# gripper_board.net
KiCad netlist of a schematic drawn in EAGLE
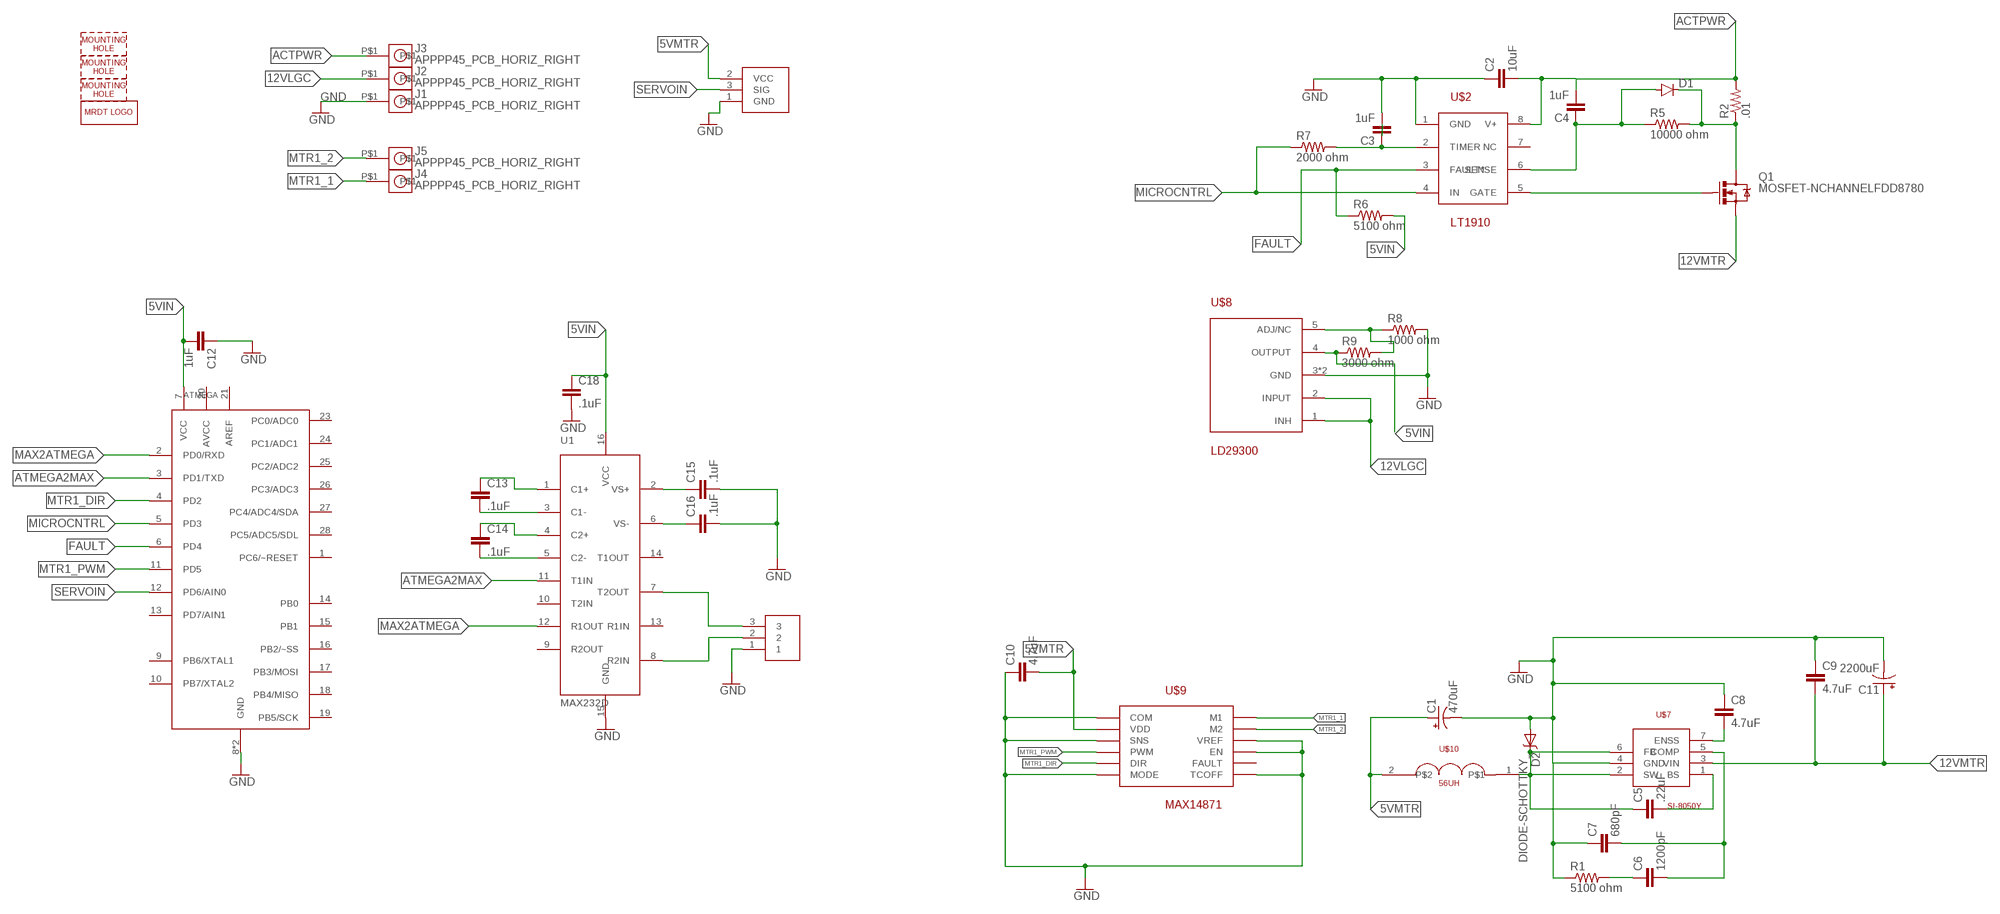
[diagram p0: schematic, sheet 1]

(export (version "E")
  (design (tool "Eeschema 10.0.6"))
  (components
    (comp (ref "ATMEGA")
      (value "Q_ATMEGA328P")
      (footprint "eagle-import:DIP28")
      (libsource (lib "eagle-import") (part "Q_ATMEGA328P"))
    )
    (comp (ref "C1")
      (value "470uF")
      (footprint "eagle-import:PANASONIC_H13")
      (libsource (lib "eagle-import") (part "100UF-ELECT"))
    )
    (comp (ref "C2")
      (value "10uF")
      (footprint "eagle-import:0603-CAP")
      (libsource (lib "eagle-import") (part "CAP0603-CAP"))
    )
    (comp (ref "C3")
      (value "1uF")
      (footprint "eagle-import:0603-CAP")
      (libsource (lib "eagle-import") (part "CAP0603-CAP"))
    )
    (comp (ref "C4")
      (value "1uF")
      (footprint "eagle-import:0603-CAP")
      (libsource (lib "eagle-import") (part "CAP0603-CAP"))
    )
    (comp (ref "C5")
      (value ".22uF")
      (footprint "eagle-import:1206")
      (libsource (lib "eagle-import") (part "1.0UF50V10%(1206)"))
    )
    (comp (ref "C6")
      (value "1200pF")
      (footprint "eagle-import:1206")
      (libsource (lib "eagle-import") (part "1.0UF50V10%(1206)"))
    )
    (comp (ref "C7")
      (value "680pF")
      (footprint "eagle-import:1206")
      (libsource (lib "eagle-import") (part "1.0UF50V10%(1206)"))
    )
    (comp (ref "C8")
      (value "4.7uF")
      (footprint "eagle-import:1206")
      (libsource (lib "eagle-import") (part "1.0UF50V10%(1206)"))
    )
    (comp (ref "C9")
      (value "4.7uF")
      (footprint "eagle-import:1206")
      (libsource (lib "eagle-import") (part "1.0UF50V10%(1206)"))
    )
    (comp (ref "C10")
      (value "4.7uF")
      (footprint "eagle-import:1206")
      (libsource (lib "eagle-import") (part "1.0UF50V10%(1206)"))
    )
    (comp (ref "C11")
      (value "2200uF")
      (footprint "eagle-import:C_16MM")
      (libsource (lib "eagle-import") (part "C_108CKH050M"))
    )
    (comp (ref "C12")
      (value "1uF")
      (footprint "eagle-import:0603-CAP")
      (libsource (lib "eagle-import") (part "CAP0603-CAP"))
    )
    (comp (ref "C13")
      (value ".1uF")
      (footprint "eagle-import:0805")
      (libsource (lib "eagle-import") (part "22UF-6.3V-20%(0805)"))
    )
    (comp (ref "C14")
      (value ".1uF")
      (footprint "eagle-import:0805")
      (libsource (lib "eagle-import") (part "22UF-6.3V-20%(0805)"))
    )
    (comp (ref "C15")
      (value ".1uF")
      (footprint "eagle-import:0805")
      (libsource (lib "eagle-import") (part "22UF-6.3V-20%(0805)"))
    )
    (comp (ref "C16")
      (value ".1uF")
      (footprint "eagle-import:0805")
      (libsource (lib "eagle-import") (part "22UF-6.3V-20%(0805)"))
    )
    (comp (ref "C18")
      (value ".1uF")
      (footprint "eagle-import:0805")
      (libsource (lib "eagle-import") (part "22UF-6.3V-20%(0805)"))
    )
    (comp (ref "D1")
      (value "DIODESMA")
      (footprint "eagle-import:SMA-DIODE")
      (libsource (lib "eagle-import") (part "DIODESMA"))
    )
    (comp (ref "D2")
      (value "DIODE-SCHOTTKY_")
      (footprint "eagle-import:SMA-DIODE")
      (libsource (lib "eagle-import") (part "DIODE-SCHOTTKY_"))
    )
    (comp (ref "H1")
      (value "MOUNTING_HOLE#4")
      (footprint "eagle-import:#4_SCREW")
      (libsource (lib "eagle-import") (part "MOUNTING_HOLE#4"))
    )
    (comp (ref "H2")
      (value "MOUNTING_HOLE#4")
      (footprint "eagle-import:#4_SCREW")
      (libsource (lib "eagle-import") (part "MOUNTING_HOLE#4"))
    )
    (comp (ref "H3")
      (value "MOUNTING_HOLE#4")
      (footprint "eagle-import:#4_SCREW")
      (libsource (lib "eagle-import") (part "MOUNTING_HOLE#4"))
    )
    (comp (ref "J1")
      (value "APPPP45_PCB_HORIZ_RIGHT")
      (footprint "eagle-import:APP45_PCB_HORIZ_RIGHT")
      (libsource (lib "eagle-import") (part "APPPP45_PCB_HORIZ_RIGHT"))
    )
    (comp (ref "J2")
      (value "APPPP45_PCB_HORIZ_RIGHT")
      (footprint "eagle-import:APP45_PCB_HORIZ_RIGHT")
      (libsource (lib "eagle-import") (part "APPPP45_PCB_HORIZ_RIGHT"))
    )
    (comp (ref "J3")
      (value "APPPP45_PCB_HORIZ_RIGHT")
      (footprint "eagle-import:APP45_PCB_HORIZ_RIGHT")
      (libsource (lib "eagle-import") (part "APPPP45_PCB_HORIZ_RIGHT"))
    )
    (comp (ref "J4")
      (value "APPPP45_PCB_HORIZ_RIGHT")
      (footprint "eagle-import:APP45_PCB_HORIZ_RIGHT")
      (libsource (lib "eagle-import") (part "APPPP45_PCB_HORIZ_RIGHT"))
    )
    (comp (ref "J5")
      (value "APPPP45_PCB_HORIZ_RIGHT")
      (footprint "eagle-import:APP45_PCB_HORIZ_RIGHT")
      (libsource (lib "eagle-import") (part "APPPP45_PCB_HORIZ_RIGHT"))
    )
    (comp (ref "J6")
      (value "SL03")
      (footprint "eagle-import:MOLEX-70543-0002")
      (libsource (lib "eagle-import") (part "SL03"))
    )
    (comp (ref "LOGO1")
      (value "MRDT_LOGO")
      (footprint "eagle-import:MRDT_LOGO")
      (libsource (lib "eagle-import") (part "MRDT_LOGO"))
    )
    (comp (ref "Q1")
      (value "MOSFET-NCHANNELFDD8780")
      (footprint "eagle-import:DPAK")
      (libsource (lib "eagle-import") (part "MOSFET-NCHANNELFDD8780"))
    )
    (comp (ref "R1")
      (value "5100 ohm")
      (footprint "eagle-import:0603-RES")
      (libsource (lib "eagle-import") (part "RESISTOR0603-RES"))
    )
    (comp (ref "R2")
      (value ".01")
      (footprint "eagle-import:1206")
      (libsource (lib "eagle-import") (part "SparkFun-Resistors_RESISTOR1206"))
    )
    (comp (ref "R5")
      (value "10000 ohm")
      (footprint "eagle-import:0603-RES")
      (libsource (lib "eagle-import") (part "RESISTOR0603-RES"))
    )
    (comp (ref "R6")
      (value "5100 ohm")
      (footprint "eagle-import:0603-RES")
      (libsource (lib "eagle-import") (part "RESISTOR0603-RES"))
    )
    (comp (ref "R7")
      (value "2000 ohm")
      (footprint "eagle-import:0603-RES")
      (libsource (lib "eagle-import") (part "RESISTOR0603-RES"))
    )
    (comp (ref "R8")
      (value "1000 ohm")
      (footprint "eagle-import:0603-RES")
      (libsource (lib "eagle-import") (part "RESISTOR0603-RES"))
    )
    (comp (ref "R9")
      (value "3000 ohm")
      (footprint "eagle-import:0603-RES")
      (libsource (lib "eagle-import") (part "RESISTOR0603-RES"))
    )
    (comp (ref "U$1")
      (value "SERVOMOLEX_SL_VERT_TH")
      (footprint "eagle-import:MOLEX-70543-0002")
      (libsource (lib "eagle-import") (part "SERVOMOLEX_SL_VERT_TH"))
    )
    (comp (ref "U$2")
      (value "LT1910")
      (footprint "eagle-import:SOIC8")
      (libsource (lib "eagle-import") (part "LT1910"))
    )
    (comp (ref "U$7")
      (value "SI-8050Y")
      (footprint "eagle-import:TO-220-7")
      (libsource (lib "eagle-import") (part "SI-8050Y"))
    )
    (comp (ref "U$8")
      (value "LD29300")
      (footprint "eagle-import:P2PAK")
      (libsource (lib "eagle-import") (part "LD29300"))
    )
    (comp (ref "U$9")
      (value "MAX14871")
      (footprint "eagle-import:TSSOP-16")
      (libsource (lib "eagle-import") (part "MAX14871"))
    )
    (comp (ref "U$10")
      (value "56UH")
      (footprint "eagle-import:1210")
      (libsource (lib "eagle-import") (part "56UH"))
    )
    (comp (ref "U1")
      (value "MAX232D")
      (footprint "eagle-import:SOIC16")
      (libsource (lib "eagle-import") (part "MAX232D"))
    )
  )
  (nets
    (net (code "1") (name "5VIN") (class "Default")
      (node (ref "ATMEGA") (pin "7") (pinfunction "VCC_7") (pintype "bidirectional"))
      (node (ref "C12") (pin "2") (pinfunction "2_2") (pintype "passive"))
      (node (ref "C18") (pin "1") (pinfunction "1_1") (pintype "passive"))
      (node (ref "R6") (pin "2") (pinfunction "2_2") (pintype "passive"))
      (node (ref "R9") (pin "1") (pinfunction "1_1") (pintype "passive"))
      (node (ref "U$8") (pin "4") (pinfunction "OUTPUT_4") (pintype "bidirectional"))
      (node (ref "U1") (pin "16") (pinfunction "VCC_16") (pintype "bidirectional"))
    )
    (net (code "2") (name "5VMTR") (class "Default")
      (node (ref "C1") (pin "+") (pinfunction "+_+") (pintype "passive"))
      (node (ref "C10") (pin "2") (pinfunction "2_2") (pintype "passive"))
      (node (ref "U$1") (pin "2") (pinfunction "VCC_2") (pintype "bidirectional"))
      (node (ref "U$10") (pin "2") (pinfunction "P$2_2") (pintype "bidirectional"))
      (node (ref "U$9") (pin "13") (pinfunction "VDD_13") (pintype "bidirectional"))
      (node (ref "U$9") (pin "4") (pinfunction "VDD_4") (pintype "bidirectional"))
    )
    (net (code "3") (name "12VLGC") (class "Default")
      (node (ref "J2") (pin "P$1") (pinfunction "P$1_P$1") (pintype "bidirectional"))
      (node (ref "U$8") (pin "1") (pinfunction "INH_1") (pintype "bidirectional"))
      (node (ref "U$8") (pin "2") (pinfunction "INPUT_2") (pintype "bidirectional"))
    )
    (net (code "4") (name "12VMTR") (class "Default")
      (node (ref "C11") (pin "+") (pinfunction "+_+") (pintype "passive"))
      (node (ref "C9") (pin "2") (pinfunction "2_2") (pintype "passive"))
      (node (ref "Q1") (pin "3") (pinfunction "S_3") (pintype "passive"))
      (node (ref "U$7") (pin "3") (pinfunction "VIN_3") (pintype "bidirectional"))
    )
    (net (code "5") (name "ACTPWR") (class "Default")
      (node (ref "C2") (pin "2") (pinfunction "2_2") (pintype "passive"))
      (node (ref "C4") (pin "2") (pinfunction "2_2") (pintype "passive"))
      (node (ref "J3") (pin "P$1") (pinfunction "P$1_P$1") (pintype "bidirectional"))
      (node (ref "R2") (pin "2") (pinfunction "2_2") (pintype "passive"))
      (node (ref "U$2") (pin "8") (pinfunction "V+_8") (pintype "bidirectional"))
    )
    (net (code "6") (name "ATMEGA2MAX") (class "Default")
      (node (ref "ATMEGA") (pin "3") (pinfunction "PD1/TXD_3") (pintype "bidirectional"))
      (node (ref "U1") (pin "11") (pinfunction "T1IN_11") (pintype "bidirectional"))
    )
    (net (code "7") (name "FAULT") (class "Default")
      (node (ref "ATMEGA") (pin "6") (pinfunction "PD4_6") (pintype "bidirectional"))
      (node (ref "R6") (pin "1") (pinfunction "1_1") (pintype "passive"))
      (node (ref "U$2") (pin "3") (pinfunction "FAULT*_3") (pintype "bidirectional"))
    )
    (net (code "8") (name "GND") (class "Default")
      (node (ref "ATMEGA") (pin "22") (pinfunction "GND_22") (pintype "bidirectional"))
      (node (ref "ATMEGA") (pin "8") (pinfunction "GND_8") (pintype "bidirectional"))
      (node (ref "C1") (pin "-") (pinfunction "-_-") (pintype "passive"))
      (node (ref "C10") (pin "1") (pinfunction "1_1") (pintype "passive"))
      (node (ref "C11") (pin "GND") (pinfunction "-_GND") (pintype "passive"))
      (node (ref "C12") (pin "1") (pinfunction "1_1") (pintype "passive"))
      (node (ref "C15") (pin "2") (pinfunction "2_2") (pintype "passive"))
      (node (ref "C16") (pin "2") (pinfunction "2_2") (pintype "passive"))
      (node (ref "C18") (pin "2") (pinfunction "2_2") (pintype "passive"))
      (node (ref "C2") (pin "1") (pinfunction "1_1") (pintype "passive"))
      (node (ref "C3") (pin "2") (pinfunction "2_2") (pintype "passive"))
      (node (ref "C7") (pin "1") (pinfunction "1_1") (pintype "passive"))
      (node (ref "C8") (pin "1") (pinfunction "1_1") (pintype "passive"))
      (node (ref "C9") (pin "1") (pinfunction "1_1") (pintype "passive"))
      (node (ref "D2") (pin "A") (pinfunction "A_A") (pintype "passive"))
      (node (ref "J1") (pin "P$1") (pinfunction "P$1_P$1") (pintype "bidirectional"))
      (node (ref "J6") (pin "1") (pinfunction "1_1") (pintype "bidirectional"))
      (node (ref "R1") (pin "1") (pinfunction "1_1") (pintype "passive"))
      (node (ref "R8") (pin "2") (pinfunction "2_2") (pintype "passive"))
      (node (ref "U$1") (pin "1") (pinfunction "GND_1") (pintype "bidirectional"))
      (node (ref "U$2") (pin "1") (pinfunction "GND_1") (pintype "bidirectional"))
      (node (ref "U$7") (pin "4") (pinfunction "GND_4") (pintype "bidirectional"))
      (node (ref "U$8") (pin "3") (pinfunction "GND_3") (pintype "bidirectional"))
      (node (ref "U$8") (pin "P$1") (pinfunction "GND_P$1") (pintype "bidirectional"))
      (node (ref "U$9") (pin "1") (pinfunction "COM_1") (pintype "bidirectional"))
      (node (ref "U$9") (pin "11") (pinfunction "EN_11") (pintype "bidirectional"))
      (node (ref "U$9") (pin "12") (pinfunction "VREF_12") (pintype "bidirectional"))
      (node (ref "U$9") (pin "16") (pinfunction "COM_16") (pintype "bidirectional"))
      (node (ref "U$9") (pin "5") (pinfunction "SNS_5") (pintype "bidirectional"))
      (node (ref "U$9") (pin "8") (pinfunction "MODE_8") (pintype "bidirectional"))
      (node (ref "U$9") (pin "9") (pinfunction "TCOFF_9") (pintype "bidirectional"))
      (node (ref "U1") (pin "15") (pinfunction "GND_15") (pintype "bidirectional"))
    )
    (net (code "9") (name "MAX2ATMEGA") (class "Default")
      (node (ref "ATMEGA") (pin "2") (pinfunction "PD0/RXD_2") (pintype "bidirectional"))
      (node (ref "U1") (pin "12") (pinfunction "R1OUT_12") (pintype "bidirectional"))
    )
    (net (code "10") (name "MICROCNTRL") (class "Default")
      (node (ref "ATMEGA") (pin "5") (pinfunction "PD3_5") (pintype "bidirectional"))
      (node (ref "R7") (pin "1") (pinfunction "1_1") (pintype "passive"))
      (node (ref "U$2") (pin "4") (pinfunction "IN_4") (pintype "bidirectional"))
    )
    (net (code "11") (name "MTR1_1") (class "Default")
      (node (ref "J4") (pin "P$1") (pinfunction "P$1_P$1") (pintype "bidirectional"))
      (node (ref "U$9") (pin "2") (pinfunction "M1_2") (pintype "bidirectional"))
      (node (ref "U$9") (pin "3") (pinfunction "M1_3") (pintype "bidirectional"))
    )
    (net (code "12") (name "MTR1_2") (class "Default")
      (node (ref "J5") (pin "P$1") (pinfunction "P$1_P$1") (pintype "bidirectional"))
      (node (ref "U$9") (pin "14") (pinfunction "M2_14") (pintype "bidirectional"))
      (node (ref "U$9") (pin "15") (pinfunction "M2_15") (pintype "bidirectional"))
    )
    (net (code "13") (name "MTR1_DIR") (class "Default")
      (node (ref "ATMEGA") (pin "4") (pinfunction "PD2_4") (pintype "bidirectional"))
      (node (ref "U$9") (pin "7") (pinfunction "DIR_7") (pintype "bidirectional"))
    )
    (net (code "14") (name "MTR1_PWM") (class "Default")
      (node (ref "ATMEGA") (pin "11") (pinfunction "PD5_11") (pintype "bidirectional"))
      (node (ref "U$9") (pin "6") (pinfunction "PWM_6") (pintype "bidirectional"))
    )
    (net (code "15") (name "Net-(C6-Pad1)") (class "Default")
      (node (ref "C6") (pin "1") (pinfunction "1_1") (pintype "passive"))
      (node (ref "R1") (pin "2") (pinfunction "2_2") (pintype "passive"))
    )
    (net (code "16") (name "Net-(Q1-D)") (class "Default")
      (node (ref "D1") (pin "C") (pinfunction "C_C") (pintype "passive"))
      (node (ref "Q1") (pin "4") (pinfunction "D_4") (pintype "passive"))
      (node (ref "R2") (pin "1") (pinfunction "1_1") (pintype "passive"))
      (node (ref "R5") (pin "2") (pinfunction "2_2") (pintype "passive"))
    )
    (net (code "17") (name "Net-(Q1-G)") (class "Default")
      (node (ref "Q1") (pin "1") (pinfunction "G_1") (pintype "passive"))
      (node (ref "U$2") (pin "5") (pinfunction "GATE_5") (pintype "bidirectional"))
    )
    (net (code "18") (name "Net-(U$2-SENSE)") (class "Default")
      (node (ref "C4") (pin "1") (pinfunction "1_1") (pintype "passive"))
      (node (ref "D1") (pin "A") (pinfunction "A_A") (pintype "passive"))
      (node (ref "R5") (pin "1") (pinfunction "1_1") (pintype "passive"))
      (node (ref "U$2") (pin "6") (pinfunction "SENSE_6") (pintype "bidirectional"))
    )
    (net (code "19") (name "Net-(U$2-TIMER)") (class "Default")
      (node (ref "C3") (pin "1") (pinfunction "1_1") (pintype "passive"))
      (node (ref "R7") (pin "2") (pinfunction "2_2") (pintype "passive"))
      (node (ref "U$2") (pin "2") (pinfunction "TIMER_2") (pintype "bidirectional"))
    )
    (net (code "20") (name "Net-(U$7-BS)") (class "Default")
      (node (ref "C5") (pin "2") (pinfunction "2_2") (pintype "passive"))
      (node (ref "U$7") (pin "1") (pinfunction "BS_1") (pintype "bidirectional"))
    )
    (net (code "21") (name "Net-(U$7-COMP)") (class "Default")
      (node (ref "C6") (pin "2") (pinfunction "2_2") (pintype "passive"))
      (node (ref "C7") (pin "2") (pinfunction "2_2") (pintype "passive"))
      (node (ref "U$7") (pin "5") (pinfunction "COMP_5") (pintype "bidirectional"))
    )
    (net (code "22") (name "Net-(U$7-ENSS)") (class "Default")
      (node (ref "C8") (pin "2") (pinfunction "2_2") (pintype "passive"))
      (node (ref "U$7") (pin "7") (pinfunction "ENSS_7") (pintype "bidirectional"))
    )
    (net (code "23") (name "Net-(U$8-ADJ{slash}NC)") (class "Default")
      (node (ref "R8") (pin "1") (pinfunction "1_1") (pintype "passive"))
      (node (ref "R9") (pin "2") (pinfunction "2_2") (pintype "passive"))
      (node (ref "U$8") (pin "5") (pinfunction "ADJ/NC_5") (pintype "bidirectional"))
    )
    (net (code "24") (name "Net-(U$10-P$1)") (class "Default")
      (node (ref "C5") (pin "1") (pinfunction "1_1") (pintype "passive"))
      (node (ref "D2") (pin "C") (pinfunction "C_C") (pintype "passive"))
      (node (ref "U$10") (pin "1") (pinfunction "P$1_1") (pintype "bidirectional"))
      (node (ref "U$7") (pin "2") (pinfunction "SW_2") (pintype "bidirectional"))
      (node (ref "U$7") (pin "6") (pinfunction "FB_6") (pintype "bidirectional"))
    )
    (net (code "25") (name "Net-(U1-C1+)") (class "Default")
      (node (ref "C13") (pin "1") (pinfunction "1_1") (pintype "passive"))
      (node (ref "U1") (pin "1") (pinfunction "C1+_1") (pintype "bidirectional"))
    )
    (net (code "26") (name "Net-(U1-C1-)") (class "Default")
      (node (ref "C13") (pin "2") (pinfunction "2_2") (pintype "passive"))
      (node (ref "U1") (pin "3") (pinfunction "C1-_3") (pintype "bidirectional"))
    )
    (net (code "27") (name "Net-(U1-C2+)") (class "Default")
      (node (ref "C14") (pin "1") (pinfunction "1_1") (pintype "passive"))
      (node (ref "U1") (pin "4") (pinfunction "C2+_4") (pintype "bidirectional"))
    )
    (net (code "28") (name "Net-(U1-C2-)") (class "Default")
      (node (ref "C14") (pin "2") (pinfunction "2_2") (pintype "passive"))
      (node (ref "U1") (pin "5") (pinfunction "C2-_5") (pintype "bidirectional"))
    )
    (net (code "29") (name "Net-(U1-R2IN)") (class "Default")
      (node (ref "J6") (pin "2") (pinfunction "2_2") (pintype "bidirectional"))
      (node (ref "U1") (pin "8") (pinfunction "R2IN_8") (pintype "bidirectional"))
    )
    (net (code "30") (name "Net-(U1-T2OUT)") (class "Default")
      (node (ref "J6") (pin "3") (pinfunction "3_3") (pintype "bidirectional"))
      (node (ref "U1") (pin "7") (pinfunction "T2OUT_7") (pintype "bidirectional"))
    )
    (net (code "31") (name "Net-(U1-VS+)") (class "Default")
      (node (ref "C15") (pin "1") (pinfunction "1_1") (pintype "passive"))
      (node (ref "U1") (pin "2") (pinfunction "VS+_2") (pintype "bidirectional"))
    )
    (net (code "32") (name "Net-(U1-VS-)") (class "Default")
      (node (ref "C16") (pin "1") (pinfunction "1_1") (pintype "passive"))
      (node (ref "U1") (pin "6") (pinfunction "VS-_6") (pintype "bidirectional"))
    )
    (net (code "33") (name "SERVOIN") (class "Default")
      (node (ref "ATMEGA") (pin "12") (pinfunction "PD6/AIN0_12") (pintype "bidirectional"))
      (node (ref "U$1") (pin "3") (pinfunction "SIG_3") (pintype "bidirectional"))
    )
    (net (code "34") (name "unconnected-(ATMEGA-AREF-Pad21)") (class "Default")
      (node (ref "ATMEGA") (pin "21") (pinfunction "AREF_21") (pintype "bidirectional"))
    )
    (net (code "35") (name "unconnected-(ATMEGA-AVCC-Pad20)") (class "Default")
      (node (ref "ATMEGA") (pin "20") (pinfunction "AVCC_20") (pintype "bidirectional"))
    )
    (net (code "36") (name "unconnected-(ATMEGA-PB0-Pad14)") (class "Default")
      (node (ref "ATMEGA") (pin "14") (pinfunction "PB0_14") (pintype "bidirectional"))
    )
    (net (code "37") (name "unconnected-(ATMEGA-PB1-Pad15)") (class "Default")
      (node (ref "ATMEGA") (pin "15") (pinfunction "PB1_15") (pintype "bidirectional"))
    )
    (net (code "38") (name "unconnected-(ATMEGA-PB2{slash}~{SS}-Pad16)") (class "Default")
      (node (ref "ATMEGA") (pin "16") (pinfunction "PB2/~{SS}_16") (pintype "bidirectional"))
    )
    (net (code "39") (name "unconnected-(ATMEGA-PB3{slash}MOSI-Pad17)") (class "Default")
      (node (ref "ATMEGA") (pin "17") (pinfunction "PB3/MOSI_17") (pintype "bidirectional"))
    )
    (net (code "40") (name "unconnected-(ATMEGA-PB4{slash}MISO-Pad18)") (class "Default")
      (node (ref "ATMEGA") (pin "18") (pinfunction "PB4/MISO_18") (pintype "bidirectional"))
    )
    (net (code "41") (name "unconnected-(ATMEGA-PB5{slash}SCK-Pad19)") (class "Default")
      (node (ref "ATMEGA") (pin "19") (pinfunction "PB5/SCK_19") (pintype "bidirectional"))
    )
    (net (code "42") (name "unconnected-(ATMEGA-PB6{slash}XTAL1-Pad9)") (class "Default")
      (node (ref "ATMEGA") (pin "9") (pinfunction "PB6/XTAL1_9") (pintype "bidirectional"))
    )
    (net (code "43") (name "unconnected-(ATMEGA-PB7{slash}XTAL2-Pad10)") (class "Default")
      (node (ref "ATMEGA") (pin "10") (pinfunction "PB7/XTAL2_10") (pintype "bidirectional"))
    )
    (net (code "44") (name "unconnected-(ATMEGA-PC0{slash}ADC0-Pad23)") (class "Default")
      (node (ref "ATMEGA") (pin "23") (pinfunction "PC0/ADC0_23") (pintype "bidirectional"))
    )
    (net (code "45") (name "unconnected-(ATMEGA-PC1{slash}ADC1-Pad24)") (class "Default")
      (node (ref "ATMEGA") (pin "24") (pinfunction "PC1/ADC1_24") (pintype "bidirectional"))
    )
    (net (code "46") (name "unconnected-(ATMEGA-PC2{slash}ADC2-Pad25)") (class "Default")
      (node (ref "ATMEGA") (pin "25") (pinfunction "PC2/ADC2_25") (pintype "bidirectional"))
    )
    (net (code "47") (name "unconnected-(ATMEGA-PC3{slash}ADC3-Pad26)") (class "Default")
      (node (ref "ATMEGA") (pin "26") (pinfunction "PC3/ADC3_26") (pintype "bidirectional"))
    )
    (net (code "48") (name "unconnected-(ATMEGA-PC4{slash}ADC4{slash}SDA-Pad27)") (class "Default")
      (node (ref "ATMEGA") (pin "27") (pinfunction "PC4/ADC4/SDA_27") (pintype "bidirectional"))
    )
    (net (code "49") (name "unconnected-(ATMEGA-PC5{slash}ADC5{slash}SDL-Pad28)") (class "Default")
      (node (ref "ATMEGA") (pin "28") (pinfunction "PC5/ADC5/SDL_28") (pintype "bidirectional"))
    )
    (net (code "50") (name "unconnected-(ATMEGA-PC6{slash}~{RESET}-Pad1)") (class "Default")
      (node (ref "ATMEGA") (pin "1") (pinfunction "PC6/~{RESET}_1") (pintype "bidirectional"))
    )
    (net (code "51") (name "unconnected-(ATMEGA-PD7{slash}AIN1-Pad13)") (class "Default")
      (node (ref "ATMEGA") (pin "13") (pinfunction "PD7/AIN1_13") (pintype "bidirectional"))
    )
    (net (code "52") (name "unconnected-(U$2-NC-Pad7)") (class "Default")
      (node (ref "U$2") (pin "7") (pinfunction "NC_7") (pintype "bidirectional"))
    )
    (net (code "53") (name "unconnected-(U$9-FAULT-Pad10)") (class "Default")
      (node (ref "U$9") (pin "10") (pinfunction "FAULT_10") (pintype "bidirectional"))
    )
    (net (code "54") (name "unconnected-(U1-R1IN-Pad13)") (class "Default")
      (node (ref "U1") (pin "13") (pinfunction "R1IN_13") (pintype "bidirectional"))
    )
    (net (code "55") (name "unconnected-(U1-R2OUT-Pad9)") (class "Default")
      (node (ref "U1") (pin "9") (pinfunction "R2OUT_9") (pintype "bidirectional"))
    )
    (net (code "56") (name "unconnected-(U1-T1OUT-Pad14)") (class "Default")
      (node (ref "U1") (pin "14") (pinfunction "T1OUT_14") (pintype "bidirectional"))
    )
    (net (code "57") (name "unconnected-(U1-T2IN-Pad10)") (class "Default")
      (node (ref "U1") (pin "10") (pinfunction "T2IN_10") (pintype "bidirectional"))
    )
  )
)
